# 3pdt.net
KiCad netlist of a schematic drawn in EAGLE
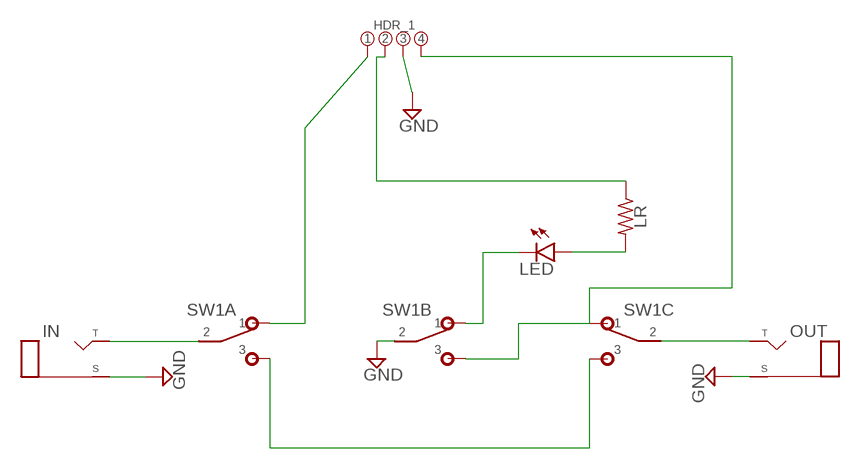
[diagram p0: schematic, sheet 1]

(export (version "E")
  (design (tool "Eeschema 10.0.6"))
  (components
    (comp (ref "HDR_1")
      (value "4PIN")
      (footprint "eagle-import:4PIN")
      (libsource (lib "eagle-import") (part "4PIN"))
    )
    (comp (ref "IN")
      (value "MONO")
      (footprint "eagle-import:TWO_PADS")
      (libsource (lib "eagle-import") (part "MONO"))
    )
    (comp (ref "LED")
      (value "LED")
      (footprint "eagle-import:3MM_D")
      (libsource (lib "eagle-import") (part "LED"))
    )
    (comp (ref "LR")
      (value "R_.1")
      (footprint "eagle-import:R0207_1V")
      (libsource (lib "eagle-import") (part "R_.1"))
    )
    (comp (ref "OUT")
      (value "MONO")
      (footprint "eagle-import:TWO_PADS")
      (libsource (lib "eagle-import") (part "MONO"))
    )
    (comp (ref "SW1")
      (value "3PDT")
      (footprint "eagle-import:3PDT")
      (libsource (lib "eagle-import") (part "3PDT"))
    )
  )
  (nets
    (net (code "1") (name "GND") (class "Default")
      (node (ref "HDR_1") (pin "P$3") (pinfunction "3_P$3") (pintype "bidirectional"))
      (node (ref "IN") (pin "S") (pinfunction "SLEEVE_S") (pintype "passive"))
      (node (ref "OUT") (pin "S") (pinfunction "SLEEVE_S") (pintype "passive"))
      (node (ref "SW1") (pin "B2") (pinfunction "2_B2") (pintype "passive"))
    )
    (net (code "2") (name "Net-(HDR_1-1)") (class "Default")
      (node (ref "HDR_1") (pin "P$1") (pinfunction "1_P$1") (pintype "bidirectional"))
      (node (ref "SW1") (pin "A1") (pinfunction "1_A1") (pintype "passive"))
    )
    (net (code "3") (name "Net-(HDR_1-2)") (class "Default")
      (node (ref "HDR_1") (pin "P$2") (pinfunction "2_P$2") (pintype "bidirectional"))
      (node (ref "LR") (pin "1") (pinfunction "1_1") (pintype "passive"))
    )
    (net (code "4") (name "Net-(HDR_1-4)") (class "Default")
      (node (ref "HDR_1") (pin "P$4") (pinfunction "4_P$4") (pintype "bidirectional"))
      (node (ref "SW1") (pin "B3") (pinfunction "3_B3") (pintype "passive"))
      (node (ref "SW1") (pin "C1") (pinfunction "1_C1") (pintype "passive"))
    )
    (net (code "5") (name "Net-(IN-TIP)") (class "Default")
      (node (ref "IN") (pin "T") (pinfunction "TIP_T") (pintype "passive"))
      (node (ref "SW1") (pin "A2") (pinfunction "2_A2") (pintype "passive"))
    )
    (net (code "6") (name "Net-(LED-A)") (class "Default")
      (node (ref "LED") (pin "ANODE") (pinfunction "A_ANODE") (pintype "passive"))
      (node (ref "LR") (pin "2") (pinfunction "2_2") (pintype "passive"))
    )
    (net (code "7") (name "Net-(LED-C)") (class "Default")
      (node (ref "LED") (pin "P$1") (pinfunction "C_P$1") (pintype "passive"))
      (node (ref "SW1") (pin "B1") (pinfunction "1_B1") (pintype "passive"))
    )
    (net (code "8") (name "Net-(OUT-TIP)") (class "Default")
      (node (ref "OUT") (pin "T") (pinfunction "TIP_T") (pintype "passive"))
      (node (ref "SW1") (pin "C2") (pinfunction "2_C2") (pintype "passive"))
    )
    (net (code "9") (name "Net-(SW1A-3)") (class "Default")
      (node (ref "SW1") (pin "A3") (pinfunction "3_A3") (pintype "passive"))
      (node (ref "SW1") (pin "C3") (pinfunction "3_C3") (pintype "passive"))
    )
  )
)
